# VeloPuter.net
KiCad netlist of a schematic drawn in EAGLE
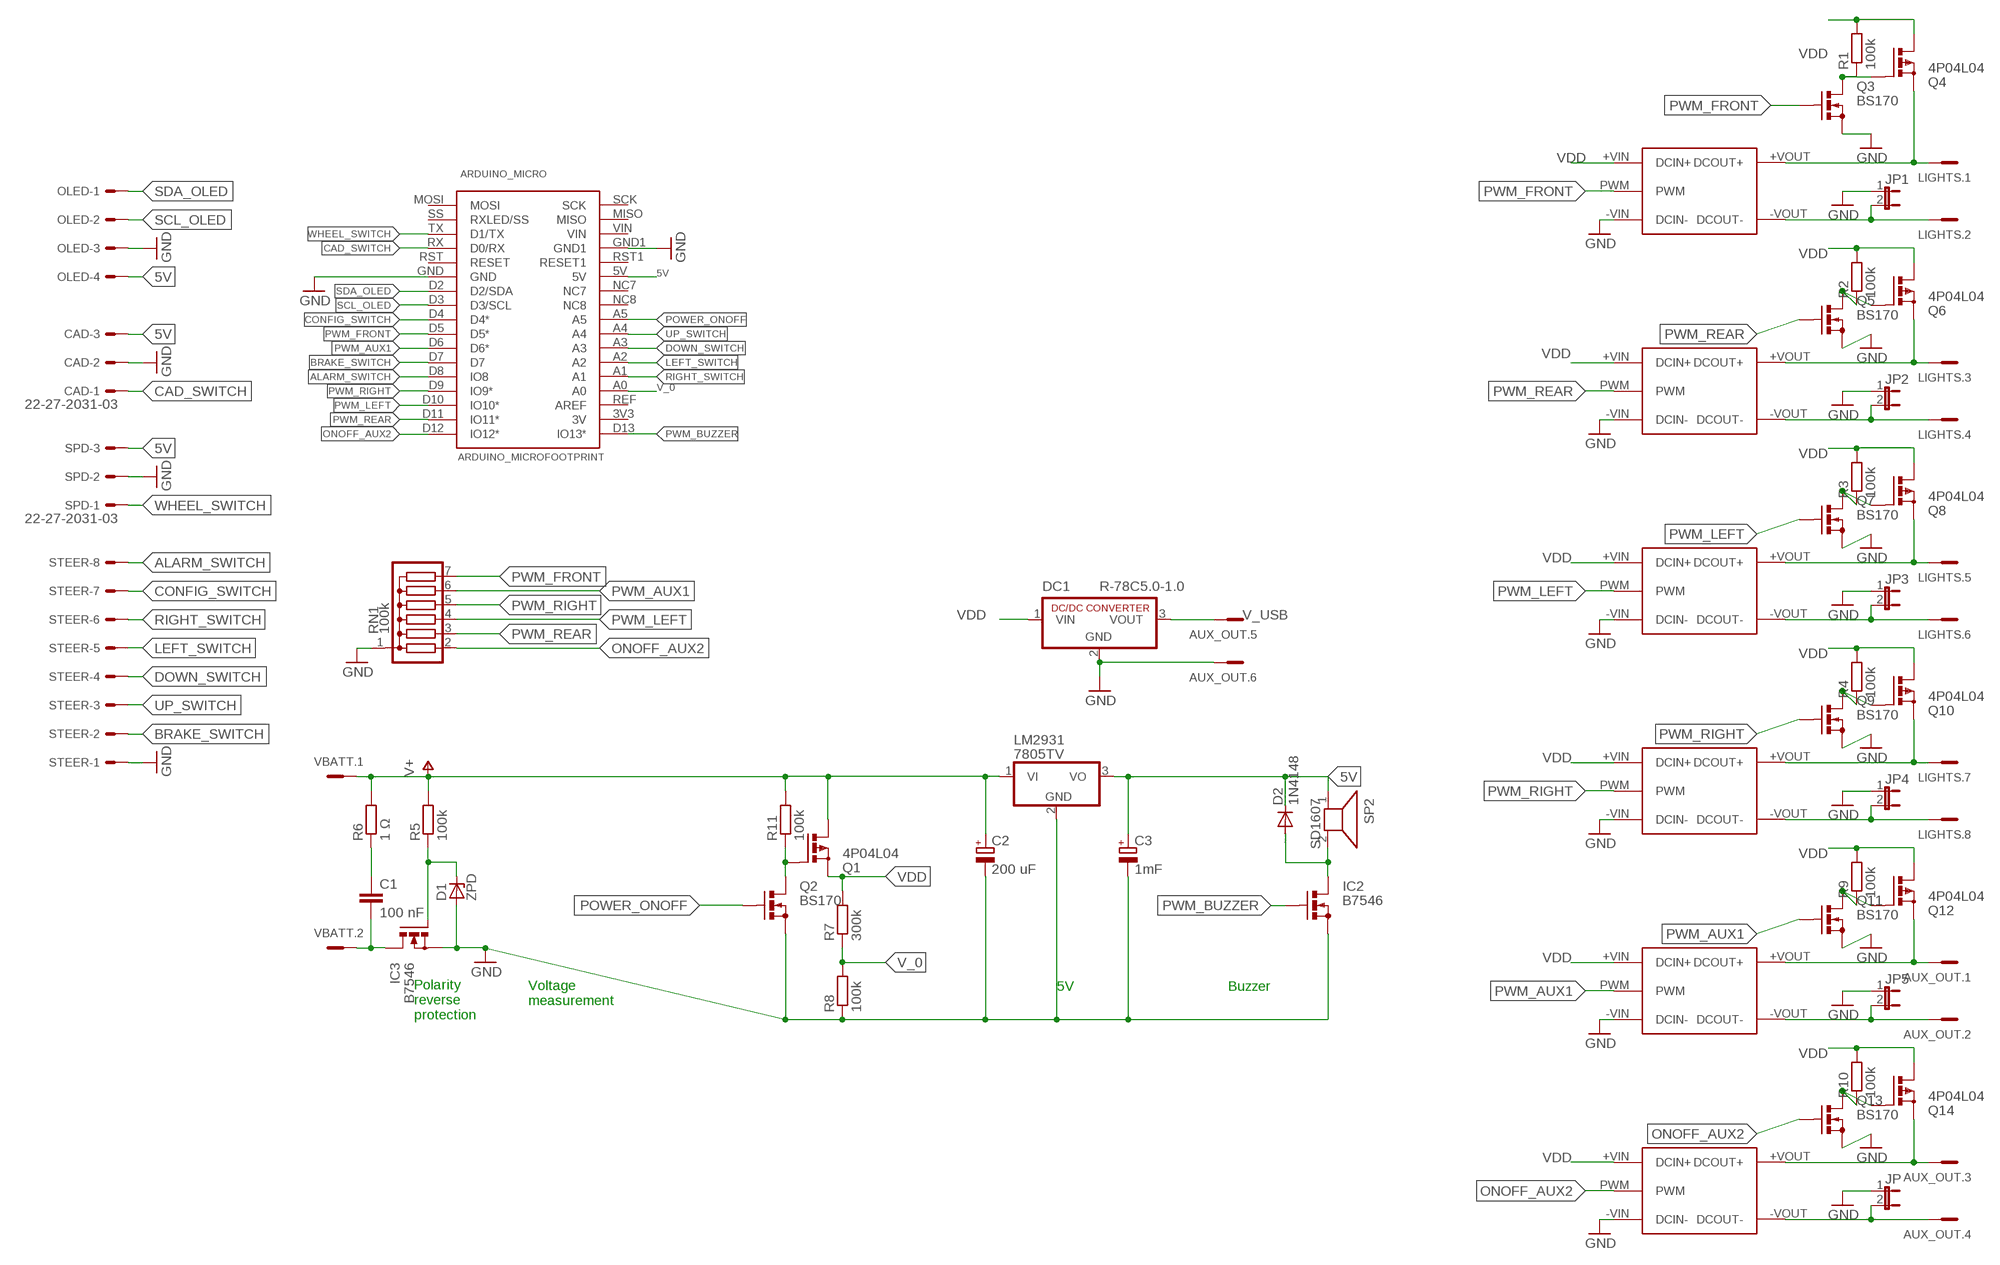
[diagram p0: schematic, sheet 1]

(export (version "E")
  (design (tool "Eeschema 10.0.6"))
  (components
    (comp (ref "ARDUINO_MICRO")
      (value "ARDUINO_MICROFOOTPRINT")
      (footprint "eagle-import:ARDUINO-MICRO")
      (libsource (lib "eagle-import") (part "ARDUINO_MICROFOOTPRINT"))
    )
    (comp (ref "AUX_OUT")
      (value "Aux")
      (footprint "eagle-import:MCV6")
      (libsource (lib "eagle-import") (part "MCV6"))
    )
    (comp (ref "BRAKE")
      (value "LDD-L")
      (footprint "eagle-import:LDD-L")
      (libsource (lib "eagle-import") (part "LDD-L"))
    )
    (comp (ref "C1")
      (value "100 nF")
      (footprint "eagle-import:C2.5-3")
      (libsource (lib "eagle-import") (part "C2,5-3"))
    )
    (comp (ref "C2")
      (value "200 uF")
      (footprint "eagle-import:E5-10,5")
      (libsource (lib "eagle-import") (part "CPOL-EUE5-10.5"))
    )
    (comp (ref "C3")
      (value "1mF")
      (footprint "eagle-import:E5-10,5")
      (libsource (lib "eagle-import") (part "resistor_CPOL-EUE5-10.5"))
    )
    (comp (ref "CAD")
      (value "22-27-2031-03")
      (footprint "eagle-import:6410-03")
      (libsource (lib "eagle-import") (part "22-?-0327-2031"))
    )
    (comp (ref "D1")
      (value "ZPD")
      (footprint "eagle-import:DO35Z10")
      (libsource (lib "eagle-import") (part "ZPD"))
    )
    (comp (ref "D2")
      (value "1N4148")
      (footprint "eagle-import:DO35-7")
      (libsource (lib "eagle-import") (part "1N4148DO35-7"))
    )
    (comp (ref "DC1")
      (value "R-78C5.0-1.0")
      (footprint "eagle-import:SIP3")
      (libsource (lib "eagle-import") (part "R-78C-1.05.0"))
    )
    (comp (ref "IC2")
      (value "B7546")
      (footprint "eagle-import:SOT54E")
      (libsource (lib "eagle-import") (part "BS170"))
    )
    (comp (ref "IC3")
      (value "B7546")
      (footprint "eagle-import:TO220BV")
      (libsource (lib "eagle-import") (part "PMOSFET_NTO220BV"))
    )
    (comp (ref "JP")
      (value "JP1E")
      (footprint "eagle-import:JP1")
      (libsource (lib "eagle-import") (part "JP1E"))
    )
    (comp (ref "JP1")
      (value "JP1E")
      (footprint "eagle-import:JP1")
      (libsource (lib "eagle-import") (part "JP1E"))
    )
    (comp (ref "JP2")
      (value "JP1E")
      (footprint "eagle-import:JP1")
      (libsource (lib "eagle-import") (part "JP1E"))
    )
    (comp (ref "JP3")
      (value "JP1E")
      (footprint "eagle-import:JP1")
      (libsource (lib "eagle-import") (part "JP1E"))
    )
    (comp (ref "JP4")
      (value "JP1E")
      (footprint "eagle-import:JP1")
      (libsource (lib "eagle-import") (part "JP1E"))
    )
    (comp (ref "JP5")
      (value "JP1E")
      (footprint "eagle-import:JP1")
      (libsource (lib "eagle-import") (part "JP1E"))
    )
    (comp (ref "LIGHTS")
      (value "Lights")
      (footprint "eagle-import:MCV8")
      (libsource (lib "eagle-import") (part "MCV8"))
    )
    (comp (ref "LM2931")
      (value "7805TV")
      (footprint "eagle-import:TO220V")
      (libsource (lib "eagle-import") (part "78TV05"))
    )
    (comp (ref "OLED")
      (value "22-27-2041-04")
      (footprint "eagle-import:6410-04")
      (libsource (lib "eagle-import") (part "22-?-0427-2041"))
    )
    (comp (ref "Q1")
      (value "4P04L04")
      (footprint "eagle-import:TO220BV")
      (libsource (lib "eagle-import") (part "PMOSFET_PTO220BV"))
    )
    (comp (ref "Q2")
      (value "BS170")
      (footprint "eagle-import:SOT54E")
      (libsource (lib "eagle-import") (part "BS170"))
    )
    (comp (ref "Q3")
      (value "BS170")
      (footprint "eagle-import:SOT54E")
      (libsource (lib "eagle-import") (part "BS170"))
    )
    (comp (ref "Q4")
      (value "4P04L04")
      (footprint "eagle-import:TO220BV")
      (libsource (lib "eagle-import") (part "PMOSFET_PTO220BV"))
    )
    (comp (ref "Q5")
      (value "BS170")
      (footprint "eagle-import:SOT54E")
      (libsource (lib "eagle-import") (part "BS170"))
    )
    (comp (ref "Q6")
      (value "4P04L04")
      (footprint "eagle-import:TO220BV")
      (libsource (lib "eagle-import") (part "PMOSFET_PTO220BV"))
    )
    (comp (ref "Q7")
      (value "BS170")
      (footprint "eagle-import:SOT54E")
      (libsource (lib "eagle-import") (part "BS170"))
    )
    (comp (ref "Q8")
      (value "4P04L04")
      (footprint "eagle-import:TO220BV")
      (libsource (lib "eagle-import") (part "PMOSFET_PTO220BV"))
    )
    (comp (ref "Q9")
      (value "BS170")
      (footprint "eagle-import:SOT54E")
      (libsource (lib "eagle-import") (part "BS170"))
    )
    (comp (ref "Q10")
      (value "4P04L04")
      (footprint "eagle-import:TO220BV")
      (libsource (lib "eagle-import") (part "PMOSFET_PTO220BV"))
    )
    (comp (ref "Q11")
      (value "BS170")
      (footprint "eagle-import:SOT54E")
      (libsource (lib "eagle-import") (part "BS170"))
    )
    (comp (ref "Q12")
      (value "4P04L04")
      (footprint "eagle-import:TO220BV")
      (libsource (lib "eagle-import") (part "PMOSFET_PTO220BV"))
    )
    (comp (ref "Q13")
      (value "BS170")
      (footprint "eagle-import:SOT54E")
      (libsource (lib "eagle-import") (part "BS170"))
    )
    (comp (ref "Q14")
      (value "4P04L04")
      (footprint "eagle-import:TO220BV")
      (libsource (lib "eagle-import") (part "PMOSFET_PTO220BV"))
    )
    (comp (ref "R1")
      (value "100k")
      (footprint "eagle-import:0207_10")
      (libsource (lib "eagle-import") (part "R-EU_0207/10"))
    )
    (comp (ref "R2")
      (value "100k")
      (footprint "eagle-import:0207_10")
      (libsource (lib "eagle-import") (part "R-EU_0207/10"))
    )
    (comp (ref "R3")
      (value "100k")
      (footprint "eagle-import:0207_10")
      (libsource (lib "eagle-import") (part "R-EU_0207/10"))
    )
    (comp (ref "R4")
      (value "100k")
      (footprint "eagle-import:0207_10")
      (libsource (lib "eagle-import") (part "R-EU_0207/10"))
    )
    (comp (ref "R5")
      (value "100k")
      (footprint "eagle-import:0207_10")
      (libsource (lib "eagle-import") (part "R-EU_0207/10"))
    )
    (comp (ref "R6")
      (value "1 Ω")
      (footprint "eagle-import:0207_10")
      (libsource (lib "eagle-import") (part "R-EU_0207/10"))
    )
    (comp (ref "R7")
      (value "300k")
      (footprint "eagle-import:0207_10")
      (libsource (lib "eagle-import") (part "R-EU_0207/10"))
    )
    (comp (ref "R8")
      (value "100k")
      (footprint "eagle-import:0207_10")
      (libsource (lib "eagle-import") (part "R-EU_0207/10"))
    )
    (comp (ref "R9")
      (value "100k")
      (footprint "eagle-import:0207_10")
      (libsource (lib "eagle-import") (part "R-EU_0207/10"))
    )
    (comp (ref "R10")
      (value "100k")
      (footprint "eagle-import:0207_10")
      (libsource (lib "eagle-import") (part "R-EU_0207/10"))
    )
    (comp (ref "R11")
      (value "100k")
      (footprint "eagle-import:0207_10")
      (libsource (lib "eagle-import") (part "R-EU_0207/10"))
    )
    (comp (ref "RN1")
      (value "100k")
      (footprint "eagle-import:SIL7")
      (libsource (lib "eagle-import") (part "G06R"))
    )
    (comp (ref "SP2")
      (value "SD1607")
      (footprint "eagle-import:AL60P")
      (libsource (lib "eagle-import") (part "AL60P"))
    )
    (comp (ref "SPD")
      (value "22-27-2031-03")
      (footprint "eagle-import:6410-03")
      (libsource (lib "eagle-import") (part "22-?-0327-2031"))
    )
    (comp (ref "STEER")
      (value "22-27-2081-08")
      (footprint "eagle-import:6410-08")
      (libsource (lib "eagle-import") (part "22-?-0827-2081"))
    )
    (comp (ref "U$1")
      (value "LDD-L")
      (footprint "eagle-import:LDD-L")
      (libsource (lib "eagle-import") (part "LDD-L"))
    )
    (comp (ref "U$2")
      (value "LDD-L")
      (footprint "eagle-import:LDD-L")
      (libsource (lib "eagle-import") (part "LDD-L"))
    )
    (comp (ref "U$3")
      (value "LDD-L")
      (footprint "eagle-import:LDD-L")
      (libsource (lib "eagle-import") (part "LDD-L"))
    )
    (comp (ref "U$4")
      (value "LDD-L")
      (footprint "eagle-import:LDD-L")
      (libsource (lib "eagle-import") (part "LDD-L"))
    )
    (comp (ref "U$5")
      (value "LDD-L")
      (footprint "eagle-import:LDD-L")
      (libsource (lib "eagle-import") (part "LDD-L"))
    )
    (comp (ref "VBATT")
      (value "MCV2")
      (footprint "eagle-import:MCV2")
      (libsource (lib "eagle-import") (part "MCV2"))
    )
  )
  (nets
    (net (code "1") (name "/V_USB") (class "Default")
      (node (ref "AUX_OUT") (pin "5") (pinfunction "SK_5") (pintype "passive"))
      (node (ref "DC1") (pin "3") (pinfunction "VOUT_3") (pintype "passive"))
    )
    (net (code "2") (name "5V") (class "Default")
      (node (ref "ARDUINO_MICRO") (pin "5V") (pinfunction "5V_5V") (pintype "bidirectional"))
      (node (ref "C3") (pin "+") (pinfunction "+_+") (pintype "passive"))
      (node (ref "CAD") (pin "3") (pinfunction "S_3") (pintype "passive"))
      (node (ref "D2") (pin "C") (pinfunction "C_C") (pintype "passive"))
      (node (ref "LM2931") (pin "3") (pinfunction "VO_3") (pintype "passive"))
      (node (ref "OLED") (pin "4") (pinfunction "S_4") (pintype "passive"))
      (node (ref "SP2") (pin "1") (pinfunction "1_1") (pintype "passive"))
      (node (ref "SPD") (pin "3") (pinfunction "S_3") (pintype "passive"))
    )
    (net (code "3") (name "ALARM_SWITCH") (class "Default")
      (node (ref "ARDUINO_MICRO") (pin "D8") (pinfunction "IO8_D8") (pintype "bidirectional"))
      (node (ref "STEER") (pin "8") (pinfunction "S_8") (pintype "passive"))
    )
    (net (code "4") (name "BRAKE_SWITCH") (class "Default")
      (node (ref "ARDUINO_MICRO") (pin "D7") (pinfunction "D7_D7") (pintype "bidirectional"))
      (node (ref "STEER") (pin "2") (pinfunction "S_2") (pintype "passive"))
    )
    (net (code "5") (name "CAD_SWITCH") (class "Default")
      (node (ref "ARDUINO_MICRO") (pin "RX") (pinfunction "D0/RX_RX") (pintype "bidirectional"))
      (node (ref "CAD") (pin "1") (pinfunction "S_1") (pintype "passive"))
    )
    (net (code "6") (name "CONFIG_SWITCH") (class "Default")
      (node (ref "ARDUINO_MICRO") (pin "D4") (pinfunction "D4*_D4") (pintype "bidirectional"))
      (node (ref "STEER") (pin "7") (pinfunction "S_7") (pintype "passive"))
    )
    (net (code "7") (name "DOWN_SWITCH") (class "Default")
      (node (ref "ARDUINO_MICRO") (pin "A3") (pinfunction "A3_A3") (pintype "bidirectional"))
      (node (ref "STEER") (pin "4") (pinfunction "S_4") (pintype "passive"))
    )
    (net (code "8") (name "GND") (class "Default")
      (node (ref "ARDUINO_MICRO") (pin "GND") (pinfunction "GND_GND") (pintype "bidirectional"))
      (node (ref "ARDUINO_MICRO") (pin "GND1") (pinfunction "GND1_GND1") (pintype "bidirectional"))
      (node (ref "AUX_OUT") (pin "6") (pinfunction "SK_6") (pintype "passive"))
      (node (ref "BRAKE") (pin "-VIN") (pinfunction "DCIN-_-VIN") (pintype "input"))
      (node (ref "C2") (pin "-") (pinfunction "-_-") (pintype "passive"))
      (node (ref "C3") (pin "-") (pinfunction "-_-") (pintype "passive"))
      (node (ref "CAD") (pin "2") (pinfunction "S_2") (pintype "passive"))
      (node (ref "D1") (pin "A") (pinfunction "A_A") (pintype "passive"))
      (node (ref "DC1") (pin "2") (pinfunction "GND_2") (pintype "passive"))
      (node (ref "IC2") (pin "S") (pinfunction "S_S") (pintype "passive"))
      (node (ref "IC3") (pin "S") (pinfunction "S_S") (pintype "passive"))
      (node (ref "JP") (pin "1") (pinfunction "1_1") (pintype "passive"))
      (node (ref "JP1") (pin "1") (pinfunction "1_1") (pintype "passive"))
      (node (ref "JP2") (pin "1") (pinfunction "1_1") (pintype "passive"))
      (node (ref "JP3") (pin "1") (pinfunction "1_1") (pintype "passive"))
      (node (ref "JP4") (pin "1") (pinfunction "1_1") (pintype "passive"))
      (node (ref "JP5") (pin "1") (pinfunction "1_1") (pintype "passive"))
      (node (ref "LM2931") (pin "2") (pinfunction "GND_2") (pintype "passive"))
      (node (ref "OLED") (pin "3") (pinfunction "S_3") (pintype "passive"))
      (node (ref "Q11") (pin "S") (pinfunction "S_S") (pintype "passive"))
      (node (ref "Q13") (pin "S") (pinfunction "S_S") (pintype "passive"))
      (node (ref "Q2") (pin "S") (pinfunction "S_S") (pintype "passive"))
      (node (ref "Q3") (pin "S") (pinfunction "S_S") (pintype "passive"))
      (node (ref "Q5") (pin "S") (pinfunction "S_S") (pintype "passive"))
      (node (ref "Q7") (pin "S") (pinfunction "S_S") (pintype "passive"))
      (node (ref "Q9") (pin "S") (pinfunction "S_S") (pintype "passive"))
      (node (ref "R8") (pin "1") (pinfunction "1_1") (pintype "passive"))
      (node (ref "RN1") (pin "1") (pinfunction "1_1") (pintype "passive"))
      (node (ref "SPD") (pin "2") (pinfunction "S_2") (pintype "passive"))
      (node (ref "STEER") (pin "1") (pinfunction "S_1") (pintype "passive"))
      (node (ref "U$1") (pin "-VIN") (pinfunction "DCIN-_-VIN") (pintype "input"))
      (node (ref "U$2") (pin "-VIN") (pinfunction "DCIN-_-VIN") (pintype "input"))
      (node (ref "U$3") (pin "-VIN") (pinfunction "DCIN-_-VIN") (pintype "input"))
      (node (ref "U$4") (pin "-VIN") (pinfunction "DCIN-_-VIN") (pintype "input"))
      (node (ref "U$5") (pin "-VIN") (pinfunction "DCIN-_-VIN") (pintype "input"))
    )
    (net (code "9") (name "LEFT_SWITCH") (class "Default")
      (node (ref "ARDUINO_MICRO") (pin "A2") (pinfunction "A2_A2") (pintype "bidirectional"))
      (node (ref "STEER") (pin "5") (pinfunction "S_5") (pintype "passive"))
    )
    (net (code "10") (name "Net-(AUX_OUTA-SK)") (class "Default")
      (node (ref "AUX_OUT") (pin "1") (pinfunction "SK_1") (pintype "passive"))
      (node (ref "Q12") (pin "S") (pinfunction "S_S") (pintype "passive"))
      (node (ref "U$5") (pin "+VOUT") (pinfunction "DCOUT+_+VOUT") (pintype "output"))
    )
    (net (code "11") (name "Net-(AUX_OUTB-SK)") (class "Default")
      (node (ref "AUX_OUT") (pin "2") (pinfunction "SK_2") (pintype "passive"))
      (node (ref "JP5") (pin "2") (pinfunction "2_2") (pintype "passive"))
      (node (ref "U$5") (pin "-VOUT") (pinfunction "DCOUT-_-VOUT") (pintype "output"))
    )
    (net (code "12") (name "Net-(AUX_OUTC-SK)") (class "Default")
      (node (ref "AUX_OUT") (pin "3") (pinfunction "SK_3") (pintype "passive"))
      (node (ref "Q14") (pin "S") (pinfunction "S_S") (pintype "passive"))
      (node (ref "U$1") (pin "+VOUT") (pinfunction "DCOUT+_+VOUT") (pintype "output"))
    )
    (net (code "13") (name "Net-(AUX_OUTD-SK)") (class "Default")
      (node (ref "AUX_OUT") (pin "4") (pinfunction "SK_4") (pintype "passive"))
      (node (ref "JP") (pin "2") (pinfunction "2_2") (pintype "passive"))
      (node (ref "U$1") (pin "-VOUT") (pinfunction "DCOUT-_-VOUT") (pintype "output"))
    )
    (net (code "14") (name "Net-(BRAKE-DCOUT+)") (class "Default")
      (node (ref "BRAKE") (pin "+VOUT") (pinfunction "DCOUT+_+VOUT") (pintype "output"))
      (node (ref "LIGHTS") (pin "3") (pinfunction "SK_3") (pintype "passive"))
      (node (ref "Q6") (pin "S") (pinfunction "S_S") (pintype "passive"))
    )
    (net (code "15") (name "Net-(BRAKE-DCOUT-)") (class "Default")
      (node (ref "BRAKE") (pin "-VOUT") (pinfunction "DCOUT-_-VOUT") (pintype "output"))
      (node (ref "JP2") (pin "2") (pinfunction "2_2") (pintype "passive"))
      (node (ref "LIGHTS") (pin "4") (pinfunction "SK_4") (pintype "passive"))
    )
    (net (code "16") (name "Net-(C1-Pad1)") (class "Default")
      (node (ref "C1") (pin "1") (pinfunction "1_1") (pintype "passive"))
      (node (ref "R6") (pin "1") (pinfunction "1_1") (pintype "passive"))
    )
    (net (code "17") (name "Net-(D1-PadC)") (class "Default")
      (node (ref "D1") (pin "C") (pinfunction "C_C") (pintype "passive"))
      (node (ref "IC3") (pin "G") (pinfunction "G_G") (pintype "passive"))
      (node (ref "R5") (pin "1") (pinfunction "1_1") (pintype "passive"))
    )
    (net (code "18") (name "Net-(D2-PadA)") (class "Default")
      (node (ref "D2") (pin "A") (pinfunction "A_A") (pintype "passive"))
      (node (ref "IC2") (pin "D") (pinfunction "D_D") (pintype "passive"))
      (node (ref "SP2") (pin "2") (pinfunction "2_2") (pintype "passive"))
    )
    (net (code "19") (name "Net-(LIGHTSA-SK)") (class "Default")
      (node (ref "LIGHTS") (pin "1") (pinfunction "SK_1") (pintype "passive"))
      (node (ref "Q4") (pin "S") (pinfunction "S_S") (pintype "passive"))
      (node (ref "U$4") (pin "+VOUT") (pinfunction "DCOUT+_+VOUT") (pintype "output"))
    )
    (net (code "20") (name "Net-(LIGHTSB-SK)") (class "Default")
      (node (ref "JP1") (pin "2") (pinfunction "2_2") (pintype "passive"))
      (node (ref "LIGHTS") (pin "2") (pinfunction "SK_2") (pintype "passive"))
      (node (ref "U$4") (pin "-VOUT") (pinfunction "DCOUT-_-VOUT") (pintype "output"))
    )
    (net (code "21") (name "Net-(LIGHTSE-SK)") (class "Default")
      (node (ref "LIGHTS") (pin "5") (pinfunction "SK_5") (pintype "passive"))
      (node (ref "Q8") (pin "S") (pinfunction "S_S") (pintype "passive"))
      (node (ref "U$2") (pin "+VOUT") (pinfunction "DCOUT+_+VOUT") (pintype "output"))
    )
    (net (code "22") (name "Net-(LIGHTSF-SK)") (class "Default")
      (node (ref "JP3") (pin "2") (pinfunction "2_2") (pintype "passive"))
      (node (ref "LIGHTS") (pin "6") (pinfunction "SK_6") (pintype "passive"))
      (node (ref "U$2") (pin "-VOUT") (pinfunction "DCOUT-_-VOUT") (pintype "output"))
    )
    (net (code "23") (name "Net-(LIGHTSG-SK)") (class "Default")
      (node (ref "LIGHTS") (pin "7") (pinfunction "SK_7") (pintype "passive"))
      (node (ref "Q10") (pin "S") (pinfunction "S_S") (pintype "passive"))
      (node (ref "U$3") (pin "+VOUT") (pinfunction "DCOUT+_+VOUT") (pintype "output"))
    )
    (net (code "24") (name "Net-(LIGHTSH-SK)") (class "Default")
      (node (ref "JP4") (pin "2") (pinfunction "2_2") (pintype "passive"))
      (node (ref "LIGHTS") (pin "8") (pinfunction "SK_8") (pintype "passive"))
      (node (ref "U$3") (pin "-VOUT") (pinfunction "DCOUT-_-VOUT") (pintype "output"))
    )
    (net (code "25") (name "Net-(Q1-PadG)") (class "Default")
      (node (ref "Q1") (pin "G") (pinfunction "G_G") (pintype "passive"))
      (node (ref "Q2") (pin "D") (pinfunction "D_D") (pintype "passive"))
      (node (ref "R11") (pin "1") (pinfunction "1_1") (pintype "passive"))
    )
    (net (code "26") (name "Net-(Q3-PadD)") (class "Default")
      (node (ref "Q3") (pin "D") (pinfunction "D_D") (pintype "passive"))
      (node (ref "Q4") (pin "G") (pinfunction "G_G") (pintype "passive"))
      (node (ref "R1") (pin "1") (pinfunction "1_1") (pintype "passive"))
    )
    (net (code "27") (name "Net-(Q5-PadD)") (class "Default")
      (node (ref "Q5") (pin "D") (pinfunction "D_D") (pintype "passive"))
      (node (ref "Q6") (pin "G") (pinfunction "G_G") (pintype "passive"))
      (node (ref "R2") (pin "1") (pinfunction "1_1") (pintype "passive"))
    )
    (net (code "28") (name "Net-(Q7-PadD)") (class "Default")
      (node (ref "Q7") (pin "D") (pinfunction "D_D") (pintype "passive"))
      (node (ref "Q8") (pin "G") (pinfunction "G_G") (pintype "passive"))
      (node (ref "R3") (pin "1") (pinfunction "1_1") (pintype "passive"))
    )
    (net (code "29") (name "Net-(Q10-PadG)") (class "Default")
      (node (ref "Q10") (pin "G") (pinfunction "G_G") (pintype "passive"))
      (node (ref "Q9") (pin "D") (pinfunction "D_D") (pintype "passive"))
      (node (ref "R4") (pin "1") (pinfunction "1_1") (pintype "passive"))
    )
    (net (code "30") (name "Net-(Q11-PadD)") (class "Default")
      (node (ref "Q11") (pin "D") (pinfunction "D_D") (pintype "passive"))
      (node (ref "Q12") (pin "G") (pinfunction "G_G") (pintype "passive"))
      (node (ref "R9") (pin "1") (pinfunction "1_1") (pintype "passive"))
    )
    (net (code "31") (name "Net-(Q13-PadD)") (class "Default")
      (node (ref "Q13") (pin "D") (pinfunction "D_D") (pintype "passive"))
      (node (ref "Q14") (pin "G") (pinfunction "G_G") (pintype "passive"))
      (node (ref "R10") (pin "1") (pinfunction "1_1") (pintype "passive"))
    )
    (net (code "32") (name "Net-(VBATTB-SK)") (class "Default")
      (node (ref "C1") (pin "2") (pinfunction "2_2") (pintype "passive"))
      (node (ref "IC3") (pin "D") (pinfunction "D_D") (pintype "passive"))
      (node (ref "VBATT") (pin "2") (pinfunction "SK_2") (pintype "passive"))
    )
    (net (code "33") (name "ONOFF_AUX2") (class "Default")
      (node (ref "ARDUINO_MICRO") (pin "D12") (pinfunction "IO12*_D12") (pintype "bidirectional"))
      (node (ref "Q13") (pin "G") (pinfunction "G_G") (pintype "passive"))
      (node (ref "RN1") (pin "2") (pinfunction "2_2") (pintype "passive"))
      (node (ref "U$1") (pin "PWM") (pinfunction "PWM_PWM") (pintype "bidirectional"))
    )
    (net (code "34") (name "POWER_ONOFF") (class "Default")
      (node (ref "ARDUINO_MICRO") (pin "A5") (pinfunction "A5_A5") (pintype "bidirectional"))
      (node (ref "Q2") (pin "G") (pinfunction "G_G") (pintype "passive"))
    )
    (net (code "35") (name "PWM_AUX1") (class "Default")
      (node (ref "ARDUINO_MICRO") (pin "D6") (pinfunction "D6*_D6") (pintype "bidirectional"))
      (node (ref "Q11") (pin "G") (pinfunction "G_G") (pintype "passive"))
      (node (ref "RN1") (pin "6") (pinfunction "6_6") (pintype "passive"))
      (node (ref "U$5") (pin "PWM") (pinfunction "PWM_PWM") (pintype "bidirectional"))
    )
    (net (code "36") (name "PWM_BUZZER") (class "Default")
      (node (ref "ARDUINO_MICRO") (pin "D13") (pinfunction "IO13*_D13") (pintype "bidirectional"))
      (node (ref "IC2") (pin "G") (pinfunction "G_G") (pintype "passive"))
    )
    (net (code "37") (name "PWM_FRONT") (class "Default")
      (node (ref "ARDUINO_MICRO") (pin "D5") (pinfunction "D5*_D5") (pintype "bidirectional"))
      (node (ref "Q3") (pin "G") (pinfunction "G_G") (pintype "passive"))
      (node (ref "RN1") (pin "7") (pinfunction "7_7") (pintype "passive"))
      (node (ref "U$4") (pin "PWM") (pinfunction "PWM_PWM") (pintype "bidirectional"))
    )
    (net (code "38") (name "PWM_LEFT") (class "Default")
      (node (ref "ARDUINO_MICRO") (pin "D10") (pinfunction "IO10*_D10") (pintype "bidirectional"))
      (node (ref "Q7") (pin "G") (pinfunction "G_G") (pintype "passive"))
      (node (ref "RN1") (pin "4") (pinfunction "4_4") (pintype "passive"))
      (node (ref "U$2") (pin "PWM") (pinfunction "PWM_PWM") (pintype "bidirectional"))
    )
    (net (code "39") (name "PWM_REAR") (class "Default")
      (node (ref "ARDUINO_MICRO") (pin "D11") (pinfunction "IO11*_D11") (pintype "bidirectional"))
      (node (ref "BRAKE") (pin "PWM") (pinfunction "PWM_PWM") (pintype "bidirectional"))
      (node (ref "Q5") (pin "G") (pinfunction "G_G") (pintype "passive"))
      (node (ref "RN1") (pin "3") (pinfunction "3_3") (pintype "passive"))
    )
    (net (code "40") (name "PWM_RIGHT") (class "Default")
      (node (ref "ARDUINO_MICRO") (pin "D9") (pinfunction "IO9*_D9") (pintype "bidirectional"))
      (node (ref "Q9") (pin "G") (pinfunction "G_G") (pintype "passive"))
      (node (ref "RN1") (pin "5") (pinfunction "5_5") (pintype "passive"))
      (node (ref "U$3") (pin "PWM") (pinfunction "PWM_PWM") (pintype "bidirectional"))
    )
    (net (code "41") (name "RIGHT_SWITCH") (class "Default")
      (node (ref "ARDUINO_MICRO") (pin "A1") (pinfunction "A1_A1") (pintype "bidirectional"))
      (node (ref "STEER") (pin "6") (pinfunction "S_6") (pintype "passive"))
    )
    (net (code "42") (name "SCL_OLED") (class "Default")
      (node (ref "ARDUINO_MICRO") (pin "D3") (pinfunction "D3/SCL_D3") (pintype "bidirectional"))
      (node (ref "OLED") (pin "2") (pinfunction "S_2") (pintype "passive"))
    )
    (net (code "43") (name "SDA_OLED") (class "Default")
      (node (ref "ARDUINO_MICRO") (pin "D2") (pinfunction "D2/SDA_D2") (pintype "bidirectional"))
      (node (ref "OLED") (pin "1") (pinfunction "S_1") (pintype "passive"))
    )
    (net (code "44") (name "UP_SWITCH") (class "Default")
      (node (ref "ARDUINO_MICRO") (pin "A4") (pinfunction "A4_A4") (pintype "bidirectional"))
      (node (ref "STEER") (pin "3") (pinfunction "S_3") (pintype "passive"))
    )
    (net (code "45") (name "V+") (class "Default")
      (node (ref "C2") (pin "+") (pinfunction "+_+") (pintype "passive"))
      (node (ref "LM2931") (pin "1") (pinfunction "VI_1") (pintype "input"))
      (node (ref "Q1") (pin "D") (pinfunction "D_D") (pintype "passive"))
      (node (ref "R11") (pin "2") (pinfunction "2_2") (pintype "passive"))
      (node (ref "R5") (pin "2") (pinfunction "2_2") (pintype "passive"))
      (node (ref "R6") (pin "2") (pinfunction "2_2") (pintype "passive"))
      (node (ref "VBATT") (pin "1") (pinfunction "SK_1") (pintype "passive"))
    )
    (net (code "46") (name "VDD") (class "Default")
      (node (ref "BRAKE") (pin "+VIN") (pinfunction "DCIN+_+VIN") (pintype "input"))
      (node (ref "DC1") (pin "1") (pinfunction "VIN_1") (pintype "passive"))
      (node (ref "Q1") (pin "S") (pinfunction "S_S") (pintype "passive"))
      (node (ref "Q10") (pin "D") (pinfunction "D_D") (pintype "passive"))
      (node (ref "Q12") (pin "D") (pinfunction "D_D") (pintype "passive"))
      (node (ref "Q14") (pin "D") (pinfunction "D_D") (pintype "passive"))
      (node (ref "Q4") (pin "D") (pinfunction "D_D") (pintype "passive"))
      (node (ref "Q6") (pin "D") (pinfunction "D_D") (pintype "passive"))
      (node (ref "Q8") (pin "D") (pinfunction "D_D") (pintype "passive"))
      (node (ref "R1") (pin "2") (pinfunction "2_2") (pintype "passive"))
      (node (ref "R10") (pin "2") (pinfunction "2_2") (pintype "passive"))
      (node (ref "R2") (pin "2") (pinfunction "2_2") (pintype "passive"))
      (node (ref "R3") (pin "2") (pinfunction "2_2") (pintype "passive"))
      (node (ref "R4") (pin "2") (pinfunction "2_2") (pintype "passive"))
      (node (ref "R7") (pin "2") (pinfunction "2_2") (pintype "passive"))
      (node (ref "R9") (pin "2") (pinfunction "2_2") (pintype "passive"))
      (node (ref "U$1") (pin "+VIN") (pinfunction "DCIN+_+VIN") (pintype "input"))
      (node (ref "U$2") (pin "+VIN") (pinfunction "DCIN+_+VIN") (pintype "input"))
      (node (ref "U$3") (pin "+VIN") (pinfunction "DCIN+_+VIN") (pintype "input"))
      (node (ref "U$4") (pin "+VIN") (pinfunction "DCIN+_+VIN") (pintype "input"))
      (node (ref "U$5") (pin "+VIN") (pinfunction "DCIN+_+VIN") (pintype "input"))
    )
    (net (code "47") (name "V_0") (class "Default")
      (node (ref "ARDUINO_MICRO") (pin "A0") (pinfunction "A0_A0") (pintype "bidirectional"))
      (node (ref "R7") (pin "1") (pinfunction "1_1") (pintype "passive"))
      (node (ref "R8") (pin "2") (pinfunction "2_2") (pintype "passive"))
    )
    (net (code "48") (name "WHEEL_SWITCH") (class "Default")
      (node (ref "ARDUINO_MICRO") (pin "TX") (pinfunction "D1/TX_TX") (pintype "bidirectional"))
      (node (ref "SPD") (pin "1") (pinfunction "S_1") (pintype "passive"))
    )
    (net (code "49") (name "unconnected-(ARDUINO_MICRO-3V-Pad3V3)") (class "Default")
      (node (ref "ARDUINO_MICRO") (pin "3V3") (pinfunction "3V_3V3") (pintype "bidirectional"))
    )
    (net (code "50") (name "unconnected-(ARDUINO_MICRO-AREF-PadREF)") (class "Default")
      (node (ref "ARDUINO_MICRO") (pin "REF") (pinfunction "AREF_REF") (pintype "bidirectional"))
    )
    (net (code "51") (name "unconnected-(ARDUINO_MICRO-PadMISO)") (class "Default")
      (node (ref "ARDUINO_MICRO") (pin "MISO") (pinfunction "MISO_MISO") (pintype "bidirectional"))
    )
    (net (code "52") (name "unconnected-(ARDUINO_MICRO-PadMOSI)") (class "Default")
      (node (ref "ARDUINO_MICRO") (pin "MOSI") (pinfunction "MOSI_MOSI") (pintype "bidirectional"))
    )
    (net (code "53") (name "unconnected-(ARDUINO_MICRO-PadNC7)") (class "Default")
      (node (ref "ARDUINO_MICRO") (pin "NC7") (pinfunction "NC7_NC7") (pintype "bidirectional"))
    )
    (net (code "54") (name "unconnected-(ARDUINO_MICRO-PadNC8)") (class "Default")
      (node (ref "ARDUINO_MICRO") (pin "NC8") (pinfunction "NC8_NC8") (pintype "bidirectional"))
    )
    (net (code "55") (name "unconnected-(ARDUINO_MICRO-PadSCK)") (class "Default")
      (node (ref "ARDUINO_MICRO") (pin "SCK") (pinfunction "SCK_SCK") (pintype "bidirectional"))
    )
    (net (code "56") (name "unconnected-(ARDUINO_MICRO-PadVIN)") (class "Default")
      (node (ref "ARDUINO_MICRO") (pin "VIN") (pinfunction "VIN_VIN") (pintype "bidirectional"))
    )
    (net (code "57") (name "unconnected-(ARDUINO_MICRO-RESET-PadRST)") (class "Default")
      (node (ref "ARDUINO_MICRO") (pin "RST") (pinfunction "RESET_RST") (pintype "bidirectional"))
    )
    (net (code "58") (name "unconnected-(ARDUINO_MICRO-RESET1-PadRST1)") (class "Default")
      (node (ref "ARDUINO_MICRO") (pin "RST1") (pinfunction "RESET1_RST1") (pintype "bidirectional"))
    )
    (net (code "59") (name "unconnected-(ARDUINO_MICRO-RXLED{slash}SS-PadSS)") (class "Default")
      (node (ref "ARDUINO_MICRO") (pin "SS") (pinfunction "RXLED/SS_SS") (pintype "bidirectional"))
    )
  )
)
